# LDR_controlled_LED.net
KiCad netlist of a schematic drawn in Altium Designer
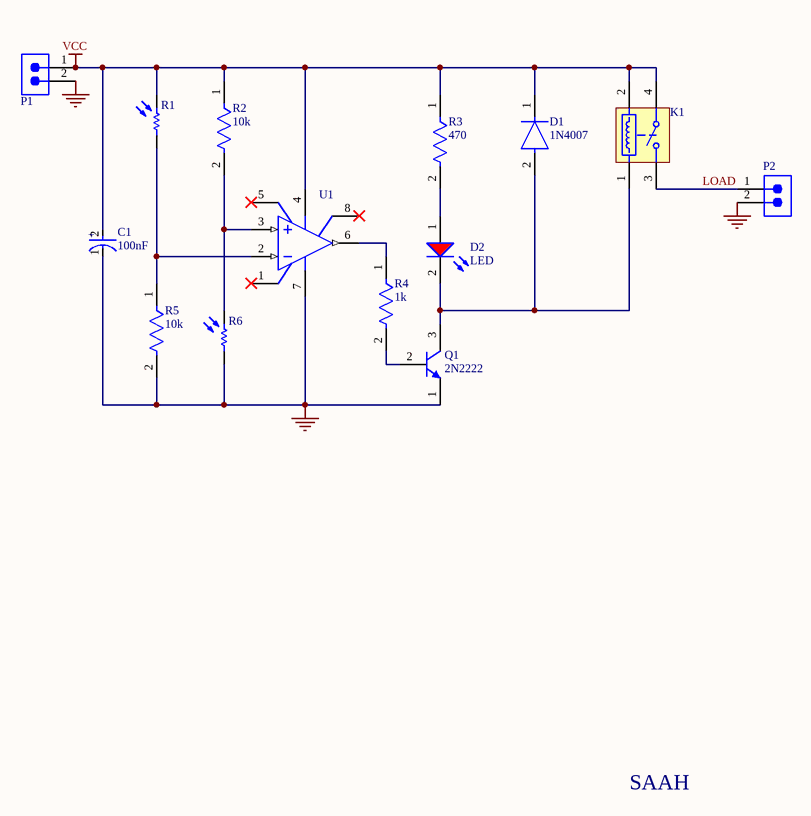
[diagram p0: LDR controlled LED.SchDoc]

(export (version "E")
  (design (tool "Eeschema 10.0.6"))
  (components
    (comp (ref "C1")
      (value "100nF")
      (footprint "FP-RAD-TH-D_12_5_0_5-L_20-MFG")
      (description "Aluminum Electrolytic Capacitors (Radial Lead Type) 10uF ±20% 450V")
      (fields (field (name "TOLERANCE") "20%") (field (name "VOLTAGE") "450V"))
      (libsource (lib "Altium Content Vault") (part "a00bbbee19879c290e62620ae7e47b1"))
    )
    (comp (ref "D1")
      (value "1N4007")
      (footprint "FP-1N4007-MFG")
      (description "Rectifier diode 1000 V 1 A DO-41, ,")
      (fields
        (field (name "MANUFACTURER") "Diotec")
        (field (name "OCTOPART") "https://octopart.com/1n4007-diotec-4040411")
      )
      (libsource (lib "Altium Content Vault") (part "d7152d700b627762746794eb795d46e"))
    )
    (comp (ref "D2")
      (value "LED")
      (footprint "WL-TMRC_D5.9H8.7")
      (description "151051SS04000 WL-TMRC THT Mono-color Round Color")
      (libsource (lib "Altium Content Vault") (part "LED_Red_1A-2K"))
    )
    (comp (ref "K1")
      (value "ALFG1PF09")
      (footprint "PNSC-LF-G-4-3010x1570x2330_V")
      (fields (field (name "MANUFACTURER") "Panasonic"))
      (libsource (lib "Altium Content Vault") (part "PNSC-ALFG1PF09-LF-G-4-3010x1570x2330-4"))
    )
    (comp (ref "P1")
      (value "653102124022")
      (footprint "653102124022")
      (libsource (lib "Altium Content Vault") (part "Header_Male_1R_02P"))
    )
    (comp (ref "P2")
      (value "653102124022")
      (footprint "653102124022")
      (libsource (lib "Altium Content Vault") (part "Header_Male_1R_02P"))
    )
    (comp (ref "Q1")
      (value "2N2222")
      (footprint "MLTC-TO-18-3")
      (description "Low Power Bipolar NPN Transistor, 30 V, -65 to 200 degC, 3-Pin TO-18, RoHS, Bulk")
      (fields (field (name "MANUFACTURER") "Multicomp"))
      (libsource (lib "Altium Content Vault") (part "BJT-NPN-EBC-3"))
    )
    (comp (ref "R1")
      (value "VT90N1")
      (footprint "EXCE-VT90N1")
      (description "Photoconductive Resistor, 200 kOhm, 100 V, 80 mW, -40 to 75 degC, 2-Pin THD, RoHS")
      (fields (field (name "MANUFACTURER") "Excelitas Technology"))
      (libsource (lib "Altium Content Vault") (part "PHOTO-RES-2"))
    )
    (comp (ref "R2")
      (value "10k")
      (footprint "FP-CF14-MFG")
      (description "RES 7.5K OHM 1/4W 5% AXIAL")
      (fields (field (name "TOLERANCE") "5%"))
      (libsource (lib "Altium Content Vault") (part "1029c3af85768c4190bb7ad29bc67b5"))
    )
    (comp (ref "R3")
      (value "470")
      (footprint "FP-CF14-MFG")
      (description "RES 7.5K OHM 1/4W 5% AXIAL")
      (fields (field (name "TOLERANCE") "5%"))
      (libsource (lib "Altium Content Vault") (part "1029c3af85768c4190bb7ad29bc67b5"))
    )
    (comp (ref "R4")
      (value "1k")
      (footprint "FP-CF14-MFG")
      (description "RES 7.5K OHM 1/4W 5% AXIAL")
      (fields (field (name "TOLERANCE") "5%"))
      (libsource (lib "Altium Content Vault") (part "1029c3af85768c4190bb7ad29bc67b5"))
    )
    (comp (ref "R5")
      (value "10k")
      (footprint "FP-CF14-MFG")
      (description "RES 7.5K OHM 1/4W 5% AXIAL")
      (fields (field (name "TOLERANCE") "5%"))
      (libsource (lib "Altium Content Vault") (part "1029c3af85768c4190bb7ad29bc67b5"))
    )
    (comp (ref "R6")
      (value "VT90N1")
      (footprint "EXCE-VT90N1")
      (description "Photoconductive Resistor, 200 kOhm, 100 V, 80 mW, -40 to 75 degC, 2-Pin THD, RoHS")
      (fields (field (name "MANUFACTURER") "Excelitas Technology"))
      (libsource (lib "Altium Content Vault") (part "PHOTO-RES-2"))
    )
    (comp (ref "U1")
      (value "LM741CN/NOPB")
      (footprint "P0008A")
      (description "Operational Amplifier, 8-pin MDIP, Pb-Free")
      (fields (field (name "MANUFACTURER") "Texas Instruments"))
      (libsource (lib "Altium Content Vault") (part "AMP-OPA-LM741-8"))
    )
  )
  (nets
    (net (code "1") (name "/LOAD") (class "Default")
      (node (ref "K1") (pin "3") (pinfunction "NO_3") (pintype "passive"))
      (node (ref "P2") (pin "1") (pinfunction "1_1") (pintype "passive"))
    )
    (net (code "2") (name "GND") (class "Default")
      (node (ref "C1") (pin "1") (pinfunction "C_1") (pintype "passive"))
      (node (ref "P1") (pin "2") (pinfunction "2_2") (pintype "passive"))
      (node (ref "P2") (pin "2") (pinfunction "2_2") (pintype "passive"))
      (node (ref "Q1") (pin "1") (pinfunction "E_1") (pintype "passive"))
      (node (ref "R5") (pin "2") (pinfunction "2_2") (pintype "passive"))
      (node (ref "R6") (pin "1") (pinfunction "1_1") (pintype "passive"))
      (node (ref "U1") (pin "7") (pinfunction "V+_7") (pintype "power_in"))
    )
    (net (code "3") (name "Net-(D1-A)") (class "Default")
      (node (ref "D1") (pin "2") (pinfunction "A_2") (pintype "passive"))
      (node (ref "D2") (pin "2") (pinfunction "K_2") (pintype "passive"))
      (node (ref "K1") (pin "1") (pinfunction "1_1") (pintype "passive"))
      (node (ref "Q1") (pin "3") (pinfunction "C_3") (pintype "passive"))
    )
    (net (code "4") (name "Net-(D2-A)") (class "Default")
      (node (ref "D2") (pin "1") (pinfunction "A_1") (pintype "passive"))
      (node (ref "R3") (pin "2") (pinfunction "2_2") (pintype "passive"))
    )
    (net (code "5") (name "Net-(Q1-B)") (class "Default")
      (node (ref "Q1") (pin "2") (pinfunction "B_2") (pintype "passive"))
      (node (ref "R4") (pin "2") (pinfunction "2_2") (pintype "passive"))
    )
    (net (code "6") (name "Net-(U1-IN+)") (class "Default")
      (node (ref "R2") (pin "2") (pinfunction "2_2") (pintype "passive"))
      (node (ref "R6") (pin "2") (pinfunction "2_2") (pintype "passive"))
      (node (ref "U1") (pin "3") (pinfunction "IN+_3") (pintype "input"))
    )
    (net (code "7") (name "Net-(U1-IN-)") (class "Default")
      (node (ref "R1") (pin "1") (pinfunction "1_1") (pintype "passive"))
      (node (ref "R5") (pin "1") (pinfunction "1_1") (pintype "passive"))
      (node (ref "U1") (pin "2") (pinfunction "IN-_2") (pintype "input"))
    )
    (net (code "8") (name "Net-(U1-OUT)") (class "Default")
      (node (ref "R4") (pin "1") (pinfunction "1_1") (pintype "passive"))
      (node (ref "U1") (pin "6") (pinfunction "OUT_6") (pintype "output"))
    )
    (net (code "9") (name "VCC") (class "Default")
      (node (ref "C1") (pin "2") (pinfunction "A_2") (pintype "passive"))
      (node (ref "D1") (pin "1") (pinfunction "C_1") (pintype "passive"))
      (node (ref "K1") (pin "2") (pinfunction "2_2") (pintype "passive"))
      (node (ref "K1") (pin "4") (pinfunction "COM_4") (pintype "passive"))
      (node (ref "P1") (pin "1") (pinfunction "1_1") (pintype "passive"))
      (node (ref "R1") (pin "2") (pinfunction "2_2") (pintype "passive"))
      (node (ref "R2") (pin "1") (pinfunction "1_1") (pintype "passive"))
      (node (ref "R3") (pin "1") (pinfunction "1_1") (pintype "passive"))
      (node (ref "U1") (pin "4") (pinfunction "V-_4") (pintype "power_in"))
    )
    (net (code "10") (name "unconnected-(U1-NC-Pad8)") (class "Default")
      (node (ref "U1") (pin "8") (pinfunction "NC_8") (pintype "passive+no_connect"))
    )
    (net (code "11") (name "unconnected-(U1-OFS_NULL-Pad1)") (class "Default")
      (node (ref "U1") (pin "1") (pinfunction "OFS_NULL_1") (pintype "passive+no_connect"))
    )
    (net (code "12") (name "unconnected-(U1-OFS_NULL-Pad5)") (class "Default")
      (node (ref "U1") (pin "5") (pinfunction "OFS_NULL_5") (pintype "passive+no_connect"))
    )
  )
)
